# 05_kbd_pm.net
KiCad netlist of a schematic drawn in Altium Designer
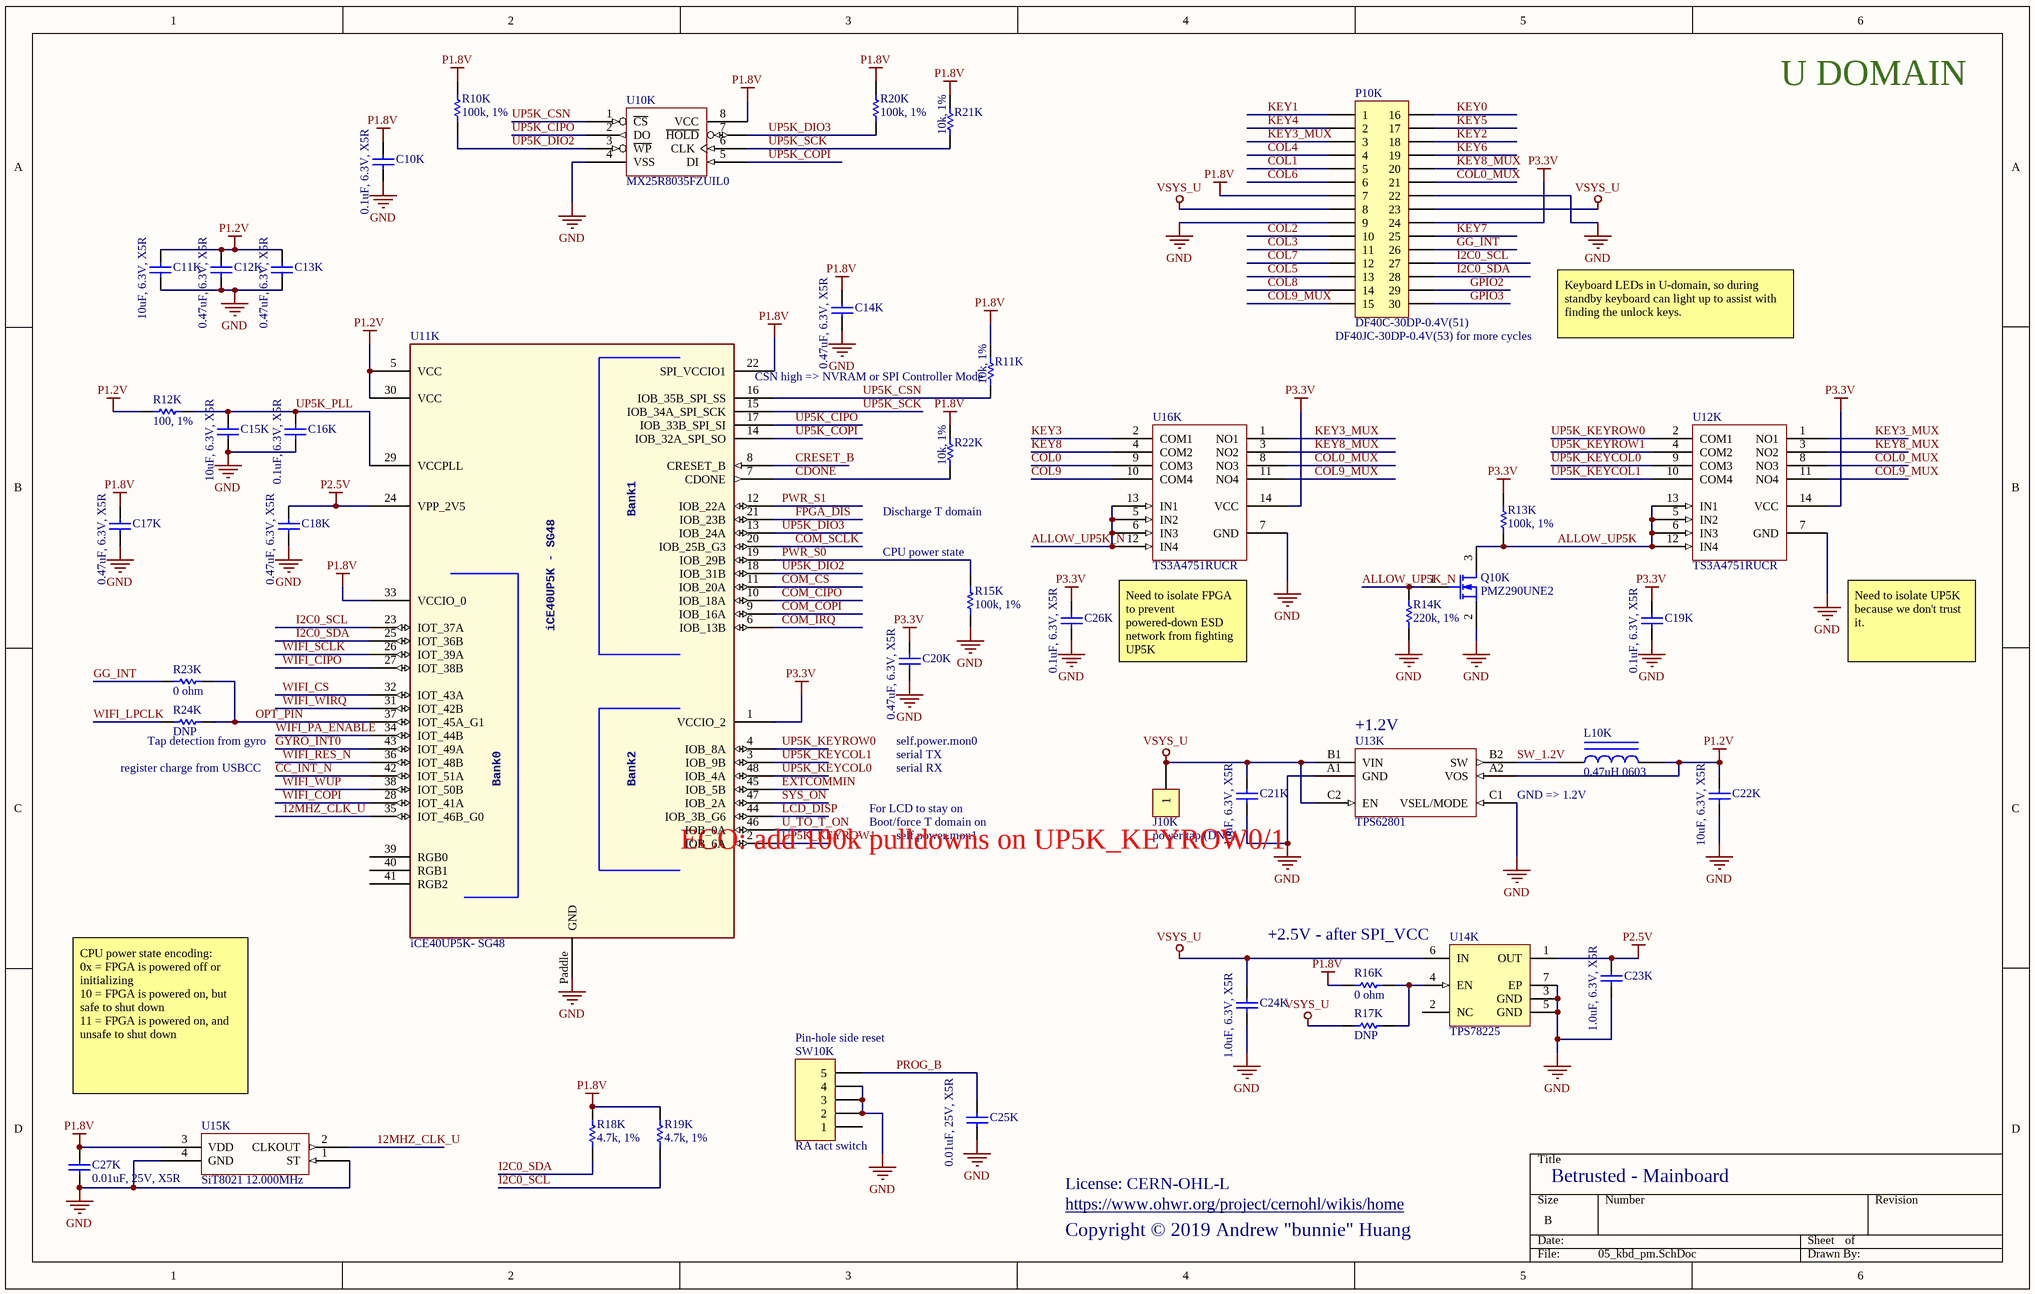
[diagram p0: 05_kbd_pm.SchDoc]

(export (version "E")
  (design (tool "Eeschema 10.0.6"))
  (components
    (comp (ref "C10K")
      (value "0.1uF, 6.3V, X5R")
      (footprint "B_CAP0201")
      (description "Capacitor (Semiconductor SIM Model)")
      (fields (field (name "MPN") "CL03A104KQ3NNNC"))
      (libsource (lib "Miscellaneous Devices") (part "Cap Semi"))
    )
    (comp (ref "C11K")
      (value "10uF, 6.3V, X5R")
      (footprint "B_CAP0603")
      (description "Capacitor (Semiconductor SIM Model)")
      (fields (field (name "MPN") "CL10A106MQ8NNNC"))
      (libsource (lib "Miscellaneous Devices") (part "Cap Semi"))
    )
    (comp (ref "C12K")
      (value "0.47uF, 6.3V, X5R")
      (footprint "B_CAP0201")
      (description "Capacitor (Semiconductor SIM Model)")
      (fields (field (name "MPN") "CL03A474KQ3NNNH"))
      (libsource (lib "Miscellaneous Devices") (part "Cap Semi"))
    )
    (comp (ref "C13K")
      (value "0.47uF, 6.3V, X5R")
      (footprint "B_CAP0201")
      (description "Capacitor (Semiconductor SIM Model)")
      (fields (field (name "MPN") "CL03A474KQ3NNNH"))
      (libsource (lib "Miscellaneous Devices") (part "Cap Semi"))
    )
    (comp (ref "C14K")
      (value "0.47uF, 6.3V, X5R")
      (footprint "B_CAP0201")
      (description "Capacitor (Semiconductor SIM Model)")
      (fields (field (name "MPN") "CL03A474KQ3NNNH"))
      (libsource (lib "Miscellaneous Devices") (part "Cap Semi"))
    )
    (comp (ref "C15K")
      (value "10uF, 6.3V, X5R")
      (footprint "B_CAP0603")
      (description "Capacitor (Semiconductor SIM Model)")
      (fields (field (name "MPN") "CL10A106MQ8NNNC"))
      (libsource (lib "Miscellaneous Devices") (part "Cap Semi"))
    )
    (comp (ref "C16K")
      (value "0.1uF, 6.3V, X5R")
      (footprint "B_CAP0201")
      (description "Capacitor (Semiconductor SIM Model)")
      (fields (field (name "MPN") "CL03A104KQ3NNNC"))
      (libsource (lib "Miscellaneous Devices") (part "Cap Semi"))
    )
    (comp (ref "C17K")
      (value "0.47uF, 6.3V, X5R")
      (footprint "B_CAP0201")
      (description "Capacitor (Semiconductor SIM Model)")
      (fields (field (name "MPN") "CL03A474KQ3NNNH"))
      (libsource (lib "Miscellaneous Devices") (part "Cap Semi"))
    )
    (comp (ref "C18K")
      (value "0.47uF, 6.3V, X5R")
      (footprint "B_CAP0201")
      (description "Capacitor (Semiconductor SIM Model)")
      (fields (field (name "MPN") "CL03A474KQ3NNNH"))
      (libsource (lib "Miscellaneous Devices") (part "Cap Semi"))
    )
    (comp (ref "C19K")
      (value "0.1uF, 6.3V, X5R")
      (footprint "B_CAP0201")
      (description "Capacitor (Semiconductor SIM Model)")
      (fields (field (name "MPN") "CL03A104KQ3NNNC"))
      (libsource (lib "Miscellaneous Devices") (part "Cap Semi"))
    )
    (comp (ref "C20K")
      (value "0.47uF, 6.3V, X5R")
      (footprint "B_CAP0201")
      (description "Capacitor (Semiconductor SIM Model)")
      (fields (field (name "MPN") "CL03A474KQ3NNNH"))
      (libsource (lib "Miscellaneous Devices") (part "Cap Semi"))
    )
    (comp (ref "C21K")
      (value "10uF, 6.3V, X5R")
      (footprint "B_CAP0603")
      (description "Capacitor (Semiconductor SIM Model)")
      (fields (field (name "MPN") "CL10A106MQ8NNNC"))
      (libsource (lib "Miscellaneous Devices") (part "Cap Semi"))
    )
    (comp (ref "C22K")
      (value "10uF, 6.3V, X5R")
      (footprint "B_CAP0603")
      (description "Capacitor (Semiconductor SIM Model)")
      (fields (field (name "MPN") "CL10A106MQ8NNNC"))
      (libsource (lib "Miscellaneous Devices") (part "Cap Semi"))
    )
    (comp (ref "C23K")
      (value "1.0uF, 6.3V, X5R")
      (footprint "B_CAP0201")
      (description "Capacitor (Semiconductor SIM Model)")
      (fields (field (name "MPN") "GRM033R60J105MEA2D"))
      (libsource (lib "Miscellaneous Devices") (part "Cap Semi"))
    )
    (comp (ref "C24K")
      (value "1.0uF, 6.3V, X5R")
      (footprint "B_CAP0201")
      (description "Capacitor (Semiconductor SIM Model)")
      (fields (field (name "MPN") "GRM033R60J105MEA2D"))
      (libsource (lib "Miscellaneous Devices") (part "Cap Semi"))
    )
    (comp (ref "C25K")
      (value "0.01uF, 25V, X5R")
      (footprint "B_RES0201")
      (description "Capacitor (Semiconductor SIM Model)")
      (fields (field (name "MPN") "GRM033R61E103KA12D"))
      (libsource (lib "Miscellaneous Devices") (part "Cap Semi"))
    )
    (comp (ref "C26K")
      (value "0.1uF, 6.3V, X5R")
      (footprint "B_CAP0201")
      (description "Capacitor (Semiconductor SIM Model)")
      (fields (field (name "MPN") "CL03A104KQ3NNNC"))
      (libsource (lib "Miscellaneous Devices") (part "Cap Semi"))
    )
    (comp (ref "C27K")
      (value "0.01uF, 25V, X5R")
      (footprint "B_RES0201")
      (description "Capacitor (Semiconductor SIM Model)")
      (fields (field (name "MPN") "GRM033R61E103KA12D"))
      (libsource (lib "Miscellaneous Devices") (part "Cap Semi"))
    )
    (comp (ref "J10K")
      (value "power tap (DNP)")
      (footprint "RESTAP-0603")
      (description "Connector")
      (fields (field (name "MPN") "DNP"))
      (libsource (lib "*") (part "CON1"))
    )
    (comp (ref "L10K")
      (value "0.47uH 0603")
      (footprint "B_IND0603")
      (description "Magnetic-Core Inductor")
      (fields (field (name "MPN") "TFM160808ALC-R47MTAA"))
      (libsource (lib "Miscellaneous Devices") (part "Inductor Iron"))
    )
    (comp (ref "P10K")
      (value "DF40C-30DP-0.4V(51)")
      (footprint "HRS_DF40C-30DP-0.4V(51)")
      (description "Header, 15-Pin, Dual row")
      (fields (field (name "PUBLISHER") "Altium Limited"))
      (libsource (lib "Miscellaneous Connectors") (part "Header 15X2A"))
    )
    (comp (ref "Q10K")
      (value "PMZ290UNE2")
      (footprint "SOT883")
      (description "N-Channel MOSFET")
      (fields (field (name "PUBLISHER") "Altium Limited"))
      (libsource (lib "Miscellaneous Devices") (part "MOSFET-N"))
    )
    (comp (ref "R10K")
      (value "100k, 1%")
      (footprint "B_RES0201")
      (description "Resistor")
      (fields (field (name "MPN") "ANY"))
      (libsource (lib "Miscellaneous Devices") (part "Res1"))
    )
    (comp (ref "R11K")
      (value "10k, 1%")
      (footprint "B_RES0201")
      (description "Resistor")
      (fields (field (name "MPN") "ANY"))
      (libsource (lib "Miscellaneous Devices") (part "Res1"))
    )
    (comp (ref "R12K")
      (value "100, 1%")
      (footprint "B_RES0402")
      (description "Resistor")
      (fields (field (name "MPN") "ANY"))
      (libsource (lib "Miscellaneous Devices") (part "Res1"))
    )
    (comp (ref "R13K")
      (value "100k, 1%")
      (footprint "B_RES0201")
      (description "Resistor")
      (fields (field (name "MPN") "ANY"))
      (libsource (lib "Miscellaneous Devices") (part "Res1"))
    )
    (comp (ref "R14K")
      (value "220k, 1%")
      (footprint "B_RES0201")
      (description "Resistor")
      (fields (field (name "MPN") "ANY"))
      (libsource (lib "Miscellaneous Devices") (part "Res1"))
    )
    (comp (ref "R15K")
      (value "100k, 1%")
      (footprint "B_RES0201")
      (description "Resistor")
      (fields (field (name "MPN") "ANY"))
      (libsource (lib "Miscellaneous Devices") (part "Res1"))
    )
    (comp (ref "R16K")
      (value "0 ohm")
      (footprint "B_RES0201")
      (description "Resistor")
      (fields (field (name "MPN") "ANY"))
      (libsource (lib "Miscellaneous Devices") (part "Res1"))
    )
    (comp (ref "R17K")
      (value "DNP")
      (footprint "B_RES0201")
      (description "Resistor")
      (fields (field (name "MPN") "ANY"))
      (libsource (lib "Miscellaneous Devices") (part "Res1"))
    )
    (comp (ref "R18K")
      (value "4.7k, 1%")
      (footprint "B_RES0201")
      (description "Resistor")
      (fields (field (name "MPN") "ANY"))
      (libsource (lib "Miscellaneous Devices") (part "Res1"))
    )
    (comp (ref "R19K")
      (value "4.7k, 1%")
      (footprint "B_RES0201")
      (description "Resistor")
      (fields (field (name "MPN") "ANY"))
      (libsource (lib "Miscellaneous Devices") (part "Res1"))
    )
    (comp (ref "R20K")
      (value "100k, 1%")
      (footprint "B_RES0201")
      (description "Resistor")
      (fields (field (name "MPN") "ANY"))
      (libsource (lib "Miscellaneous Devices") (part "Res1"))
    )
    (comp (ref "R21K")
      (value "10k, 1%")
      (footprint "B_RES0201")
      (description "Resistor")
      (fields (field (name "MPN") "ANY"))
      (libsource (lib "Miscellaneous Devices") (part "Res1"))
    )
    (comp (ref "R22K")
      (value "10k, 1%")
      (footprint "B_RES0201")
      (description "Resistor")
      (fields (field (name "MPN") "ANY"))
      (libsource (lib "Miscellaneous Devices") (part "Res1"))
    )
    (comp (ref "R23K")
      (value "0 ohm")
      (footprint "B_RES0201")
      (description "Resistor")
      (fields (field (name "MPN") "ANY"))
      (libsource (lib "Miscellaneous Devices") (part "Res1"))
    )
    (comp (ref "R24K")
      (value "DNP")
      (footprint "B_RES0201")
      (description "Resistor")
      (fields (field (name "MPN") "ANY"))
      (libsource (lib "Miscellaneous Devices") (part "Res1"))
    )
    (comp (ref "SW10K")
      (value "RA tact switch")
      (footprint "CK_KMS221GPLFS")
      (fields (field (name "MPN") "KMS221GPLFS") (field (name "PUBLISHER") "Altium Limited"))
      (libsource (lib "Miscellaneous Connectors") (part "Header 5"))
    )
    (comp (ref "U10K")
      (value "MX25R8035FZUIL0")
      (footprint "USON-8")
      (description "64Mbit SPI NOR FLASH")
      (libsource (lib "commonsch") (part "EN25P05-50GCP"))
    )
    (comp (ref "U11K")
      (value "iCE40UP5K- SG48")
      (footprint "UP5K_QFN127P600-8N")
      (fields (field (name "MPN") "ICE40UP5K-SG48I"))
      (libsource (lib "LATTICEPLDS_Library") (part "iCE40UP5K- SG48"))
    )
    (comp (ref "U12K")
      (value "TS3A4751RUCR")
      (footprint "QFN40P200X200X40-14L")
      (description "0.9 ohm low voltage, single supply, 4-channel SPST analog switch")
      (libsource (lib "commonsch-new") (part "TS3A4751RGYR"))
    )
    (comp (ref "U13K")
      (value "TPS62801")
      (footprint "BGA6C35P2X3_70X105X40_NSMD")
      (description "Buck regulator, 4MHz, 0.6A, 0.8V-1.55V, low Iq")
      (fields (field (name "MPN") "TPS62801YKAT"))
      (libsource (lib "altium-import") (part "root_0_TPS62801_"))
    )
    (comp (ref "U14K")
      (value "TPS78225")
      (footprint "TI-DRV6-1600X1000TP_V")
      (description "500nA Iq, 150mA LDO")
      (fields (field (name "MPN") "TPS78225DRVT"))
      (libsource (lib "TI-TPS78225-Q1DRV6-1600X1000TP") (part "TI-TPS78225-Q1DRV6-1600X1000TP"))
    )
    (comp (ref "U15K")
      (value "SiT8021 12.000MHz")
      (footprint "SiTIME_CSP")
      (description "1 to 26 MHz micropower oscillator")
      (fields (field (name "MPN") "SIT8021AI-J4-18S-12.000000E"))
      (libsource (lib "altium-import") (part "root_2_SiT8021_"))
    )
    (comp (ref "U16K")
      (value "TS3A4751RUCR")
      (footprint "QFN40P200X200X40-14L")
      (description "0.9 ohm low voltage, single supply, 4-channel SPST analog switch")
      (libsource (lib "commonsch-new") (part "TS3A4751RGYR"))
    )
  )
  (nets
    (net (code "1") (name "/12MHZ_CLK_U") (class "Default")
      (node (ref "U11K") (pin "35") (pinfunction "IOT_46B_G0_35") (pintype "bidirectional"))
      (node (ref "U15K") (pin "2") (pinfunction "CLKOUT_2") (pintype "output"))
    )
    (net (code "2") (name "/ALLOW_UP5K") (class "Default")
      (node (ref "Q10K") (pin "3") (pinfunction "D_3") (pintype "passive"))
      (node (ref "R13K") (pin "1") (pinfunction "1_1") (pintype "passive"))
      (node (ref "U12K") (pin "12") (pinfunction "IN4_12") (pintype "input"))
      (node (ref "U12K") (pin "13") (pinfunction "IN1_13") (pintype "input"))
      (node (ref "U12K") (pin "5") (pinfunction "IN2_5") (pintype "input"))
      (node (ref "U12K") (pin "6") (pinfunction "IN3_6") (pintype "input"))
    )
    (net (code "3") (name "/ALLOW_UP5K_N") (class "Default")
      (node (ref "Q10K") (pin "1") (pinfunction "G_1") (pintype "passive"))
      (node (ref "R14K") (pin "2") (pinfunction "2_2") (pintype "passive"))
      (node (ref "U16K") (pin "12") (pinfunction "IN4_12") (pintype "input"))
      (node (ref "U16K") (pin "13") (pinfunction "IN1_13") (pintype "input"))
      (node (ref "U16K") (pin "5") (pinfunction "IN2_5") (pintype "input"))
      (node (ref "U16K") (pin "6") (pinfunction "IN3_6") (pintype "input"))
    )
    (net (code "4") (name "/CC_INT_N") (class "Default")
      (node (ref "U11K") (pin "42") (pinfunction "IOT_51A_42") (pintype "bidirectional"))
    )
    (net (code "5") (name "/CDONE") (class "Default")
      (node (ref "R22K") (pin "2") (pinfunction "2_2") (pintype "passive"))
      (node (ref "U11K") (pin "7") (pinfunction "CDONE_7") (pintype "output"))
    )
    (net (code "6") (name "/COL0") (class "Default")
      (node (ref "U16K") (pin "9") (pinfunction "COM3_9") (pintype "passive"))
    )
    (net (code "7") (name "/COL0_MUX") (class "Default")
      (node (ref "P10K") (pin "21") (pinfunction "21_21") (pintype "passive"))
      (node (ref "U12K") (pin "8") (pinfunction "NO3_8") (pintype "passive"))
      (node (ref "U16K") (pin "8") (pinfunction "NO3_8") (pintype "passive"))
    )
    (net (code "8") (name "/COL1") (class "Default")
      (node (ref "P10K") (pin "5") (pinfunction "5_5") (pintype "passive"))
    )
    (net (code "9") (name "/COL2") (class "Default")
      (node (ref "P10K") (pin "10") (pinfunction "10_10") (pintype "passive"))
    )
    (net (code "10") (name "/COL3") (class "Default")
      (node (ref "P10K") (pin "11") (pinfunction "11_11") (pintype "passive"))
    )
    (net (code "11") (name "/COL4") (class "Default")
      (node (ref "P10K") (pin "4") (pinfunction "4_4") (pintype "passive"))
    )
    (net (code "12") (name "/COL5") (class "Default")
      (node (ref "P10K") (pin "13") (pinfunction "13_13") (pintype "passive"))
    )
    (net (code "13") (name "/COL6") (class "Default")
      (node (ref "P10K") (pin "6") (pinfunction "6_6") (pintype "passive"))
    )
    (net (code "14") (name "/COL7") (class "Default")
      (node (ref "P10K") (pin "12") (pinfunction "12_12") (pintype "passive"))
    )
    (net (code "15") (name "/COL8") (class "Default")
      (node (ref "P10K") (pin "14") (pinfunction "14_14") (pintype "passive"))
    )
    (net (code "16") (name "/COL9") (class "Default")
      (node (ref "U16K") (pin "10") (pinfunction "COM4_10") (pintype "passive"))
    )
    (net (code "17") (name "/COL9_MUX") (class "Default")
      (node (ref "P10K") (pin "15") (pinfunction "15_15") (pintype "passive"))
      (node (ref "U12K") (pin "11") (pinfunction "NO4_11") (pintype "passive"))
      (node (ref "U16K") (pin "11") (pinfunction "NO4_11") (pintype "passive"))
    )
    (net (code "18") (name "/COM_CIPO") (class "Default")
      (node (ref "U11K") (pin "10") (pinfunction "IOB_18A_10") (pintype "bidirectional"))
    )
    (net (code "19") (name "/COM_COPI") (class "Default")
      (node (ref "U11K") (pin "9") (pinfunction "IOB_16A_9") (pintype "bidirectional"))
    )
    (net (code "20") (name "/COM_CS") (class "Default")
      (node (ref "U11K") (pin "11") (pinfunction "IOB_20A_11") (pintype "bidirectional"))
    )
    (net (code "21") (name "/COM_IRQ") (class "Default")
      (node (ref "U11K") (pin "6") (pinfunction "IOB_13B_6") (pintype "bidirectional"))
    )
    (net (code "22") (name "/COM_SCLK") (class "Default")
      (node (ref "U11K") (pin "20") (pinfunction "IOB_25B_G3_20") (pintype "bidirectional"))
    )
    (net (code "23") (name "/CRESET_B") (class "Default")
      (node (ref "U11K") (pin "8") (pinfunction "CRESET_B_8") (pintype "input"))
    )
    (net (code "24") (name "/EXTCOMMIN") (class "Default")
      (node (ref "U11K") (pin "45") (pinfunction "IOB_5B_45") (pintype "bidirectional"))
    )
    (net (code "25") (name "/FPGA_DIS") (class "Default")
      (node (ref "U11K") (pin "21") (pinfunction "IOB_23B_21") (pintype "bidirectional"))
    )
    (net (code "26") (name "/GG_INT") (class "Default")
      (node (ref "P10K") (pin "26") (pinfunction "26_26") (pintype "passive"))
      (node (ref "R23K") (pin "1") (pinfunction "1_1") (pintype "passive"))
    )
    (net (code "27") (name "/GPIO2") (class "Default")
      (node (ref "P10K") (pin "29") (pinfunction "29_29") (pintype "passive"))
    )
    (net (code "28") (name "/GPIO3") (class "Default")
      (node (ref "P10K") (pin "30") (pinfunction "30_30") (pintype "passive"))
    )
    (net (code "29") (name "/GYRO_INT0") (class "Default")
      (node (ref "U11K") (pin "43") (pinfunction "IOT_49A_43") (pintype "bidirectional"))
    )
    (net (code "30") (name "/I2C0_SCL") (class "Default")
      (node (ref "P10K") (pin "27") (pinfunction "27_27") (pintype "passive"))
      (node (ref "R19K") (pin "1") (pinfunction "1_1") (pintype "passive"))
      (node (ref "U11K") (pin "23") (pinfunction "IOT_37A_23") (pintype "bidirectional"))
    )
    (net (code "31") (name "/I2C0_SDA") (class "Default")
      (node (ref "P10K") (pin "28") (pinfunction "28_28") (pintype "passive"))
      (node (ref "R18K") (pin "1") (pinfunction "1_1") (pintype "passive"))
      (node (ref "U11K") (pin "25") (pinfunction "IOT_36B_25") (pintype "bidirectional"))
    )
    (net (code "32") (name "/KEY0") (class "Default")
      (node (ref "P10K") (pin "16") (pinfunction "16_16") (pintype "passive"))
    )
    (net (code "33") (name "/KEY1") (class "Default")
      (node (ref "P10K") (pin "1") (pinfunction "1_1") (pintype "passive"))
    )
    (net (code "34") (name "/KEY2") (class "Default")
      (node (ref "P10K") (pin "18") (pinfunction "18_18") (pintype "passive"))
    )
    (net (code "35") (name "/KEY3") (class "Default")
      (node (ref "U16K") (pin "2") (pinfunction "COM1_2") (pintype "passive"))
    )
    (net (code "36") (name "/KEY3_MUX") (class "Default")
      (node (ref "P10K") (pin "3") (pinfunction "3_3") (pintype "passive"))
      (node (ref "U12K") (pin "1") (pinfunction "NO1_1") (pintype "passive"))
      (node (ref "U16K") (pin "1") (pinfunction "NO1_1") (pintype "passive"))
    )
    (net (code "37") (name "/KEY4") (class "Default")
      (node (ref "P10K") (pin "2") (pinfunction "2_2") (pintype "passive"))
    )
    (net (code "38") (name "/KEY5") (class "Default")
      (node (ref "P10K") (pin "17") (pinfunction "17_17") (pintype "passive"))
    )
    (net (code "39") (name "/KEY6") (class "Default")
      (node (ref "P10K") (pin "19") (pinfunction "19_19") (pintype "passive"))
    )
    (net (code "40") (name "/KEY7") (class "Default")
      (node (ref "P10K") (pin "25") (pinfunction "25_25") (pintype "passive"))
    )
    (net (code "41") (name "/KEY8") (class "Default")
      (node (ref "U16K") (pin "4") (pinfunction "COM2_4") (pintype "passive"))
    )
    (net (code "42") (name "/KEY8_MUX") (class "Default")
      (node (ref "P10K") (pin "20") (pinfunction "20_20") (pintype "passive"))
      (node (ref "U12K") (pin "3") (pinfunction "NO2_3") (pintype "passive"))
      (node (ref "U16K") (pin "3") (pinfunction "NO2_3") (pintype "passive"))
    )
    (net (code "43") (name "/LCD_DISP") (class "Default")
      (node (ref "U11K") (pin "44") (pinfunction "IOB_3B_G6_44") (pintype "bidirectional"))
    )
    (net (code "44") (name "/OPT_PIN") (class "Default")
      (node (ref "R23K") (pin "2") (pinfunction "2_2") (pintype "passive"))
      (node (ref "R24K") (pin "2") (pinfunction "2_2") (pintype "passive"))
      (node (ref "U11K") (pin "37") (pinfunction "IOT_45A_G1_37") (pintype "bidirectional"))
    )
    (net (code "45") (name "/PROG_B") (class "Default")
      (node (ref "C25K") (pin "1") (pinfunction "1_1") (pintype "passive"))
      (node (ref "SW10K") (pin "5") (pinfunction "5_5") (pintype "passive"))
    )
    (net (code "46") (name "/PWR_S0") (class "Default")
      (node (ref "R15K") (pin "2") (pinfunction "2_2") (pintype "passive"))
      (node (ref "U11K") (pin "19") (pinfunction "IOB_29B_19") (pintype "bidirectional"))
    )
    (net (code "47") (name "/PWR_S1") (class "Default")
      (node (ref "U11K") (pin "12") (pinfunction "IOB_22A_12") (pintype "bidirectional"))
    )
    (net (code "48") (name "/SW_1.2V") (class "Default")
      (node (ref "L10K") (pin "1") (pinfunction "1_1") (pintype "passive"))
      (node (ref "U13K") (pin "B2") (pinfunction "SW_B2") (pintype "output"))
    )
    (net (code "49") (name "/SYS_ON") (class "Default")
      (node (ref "U11K") (pin "47") (pinfunction "IOB_2A_47") (pintype "bidirectional"))
    )
    (net (code "50") (name "/UP5K_CIPO") (class "Default")
      (node (ref "U10K") (pin "2") (pinfunction "DO_2") (pintype "output"))
      (node (ref "U11K") (pin "17") (pinfunction "IOB_33B_SPI_SI_17") (pintype "passive"))
    )
    (net (code "51") (name "/UP5K_COPI") (class "Default")
      (node (ref "U10K") (pin "5") (pinfunction "DI_5") (pintype "input"))
      (node (ref "U11K") (pin "14") (pinfunction "IOB_32A_SPI_SO_14") (pintype "passive"))
    )
    (net (code "52") (name "/UP5K_CSN") (class "Default")
      (node (ref "R11K") (pin "2") (pinfunction "2_2") (pintype "passive"))
      (node (ref "U10K") (pin "1") (pinfunction "~{CS}_1") (pintype "input"))
      (node (ref "U11K") (pin "16") (pinfunction "IOB_35B_SPI_SS_16") (pintype "passive"))
    )
    (net (code "53") (name "/UP5K_DIO2") (class "Default")
      (node (ref "R10K") (pin "1") (pinfunction "1_1") (pintype "passive"))
      (node (ref "U10K") (pin "3") (pinfunction "~{WP}_3") (pintype "input"))
      (node (ref "U11K") (pin "18") (pinfunction "IOB_31B_18") (pintype "bidirectional"))
    )
    (net (code "54") (name "/UP5K_DIO3") (class "Default")
      (node (ref "R20K") (pin "1") (pinfunction "1_1") (pintype "passive"))
      (node (ref "U10K") (pin "7") (pinfunction "~{HOLD}_7") (pintype "bidirectional"))
      (node (ref "U11K") (pin "13") (pinfunction "IOB_24A_13") (pintype "bidirectional"))
    )
    (net (code "55") (name "/UP5K_KEYCOL0") (class "Default")
      (node (ref "U11K") (pin "48") (pinfunction "IOB_4A_48") (pintype "bidirectional"))
      (node (ref "U12K") (pin "9") (pinfunction "COM3_9") (pintype "passive"))
    )
    (net (code "56") (name "/UP5K_KEYCOL1") (class "Default")
      (node (ref "U11K") (pin "3") (pinfunction "IOB_9B_3") (pintype "bidirectional"))
      (node (ref "U12K") (pin "10") (pinfunction "COM4_10") (pintype "passive"))
    )
    (net (code "57") (name "/UP5K_KEYROW0") (class "Default")
      (node (ref "U11K") (pin "4") (pinfunction "IOB_8A_4") (pintype "bidirectional"))
      (node (ref "U12K") (pin "2") (pinfunction "COM1_2") (pintype "passive"))
    )
    (net (code "58") (name "/UP5K_KEYROW1") (class "Default")
      (node (ref "U11K") (pin "2") (pinfunction "IOB_6A_2") (pintype "bidirectional"))
      (node (ref "U12K") (pin "4") (pinfunction "COM2_4") (pintype "passive"))
    )
    (net (code "59") (name "/UP5K_PLL") (class "Default")
      (node (ref "C15K") (pin "1") (pinfunction "1_1") (pintype "passive"))
      (node (ref "C16K") (pin "1") (pinfunction "1_1") (pintype "passive"))
      (node (ref "R12K") (pin "1") (pinfunction "1_1") (pintype "passive"))
      (node (ref "U11K") (pin "29") (pinfunction "VCCPLL_29") (pintype "power_in"))
    )
    (net (code "60") (name "/UP5K_SCK") (class "Default")
      (node (ref "R21K") (pin "2") (pinfunction "2_2") (pintype "passive"))
      (node (ref "U10K") (pin "6") (pinfunction "CLK_6") (pintype "input"))
      (node (ref "U11K") (pin "15") (pinfunction "IOB_34A_SPI_SCK_15") (pintype "passive"))
    )
    (net (code "61") (name "/U_TO_T_ON") (class "Default")
      (node (ref "U11K") (pin "46") (pinfunction "IOB_0A_46") (pintype "bidirectional"))
    )
    (net (code "62") (name "/WIFI_CIPO") (class "Default")
      (node (ref "U11K") (pin "27") (pinfunction "IOT_38B_27") (pintype "bidirectional"))
    )
    (net (code "63") (name "/WIFI_COPI") (class "Default")
      (node (ref "U11K") (pin "28") (pinfunction "IOT_41A_28") (pintype "bidirectional"))
    )
    (net (code "64") (name "/WIFI_CS") (class "Default")
      (node (ref "U11K") (pin "32") (pinfunction "IOT_43A_32") (pintype "bidirectional"))
    )
    (net (code "65") (name "/WIFI_LPCLK") (class "Default")
      (node (ref "R24K") (pin "1") (pinfunction "1_1") (pintype "passive"))
    )
    (net (code "66") (name "/WIFI_PA_ENABLE") (class "Default")
      (node (ref "U11K") (pin "34") (pinfunction "IOT_44B_34") (pintype "bidirectional"))
    )
    (net (code "67") (name "/WIFI_RES_N") (class "Default")
      (node (ref "U11K") (pin "36") (pinfunction "IOT_48B_36") (pintype "bidirectional"))
    )
    (net (code "68") (name "/WIFI_SCLK") (class "Default")
      (node (ref "U11K") (pin "26") (pinfunction "IOT_39A_26") (pintype "bidirectional"))
    )
    (net (code "69") (name "/WIFI_WIRQ") (class "Default")
      (node (ref "U11K") (pin "31") (pinfunction "IOT_42B_31") (pintype "bidirectional"))
    )
    (net (code "70") (name "/WIFI_WUP") (class "Default")
      (node (ref "U11K") (pin "38") (pinfunction "IOT_50B_38") (pintype "bidirectional"))
    )
    (net (code "71") (name "GND") (class "Default")
      (node (ref "C10K") (pin "2") (pinfunction "2_2") (pintype "passive"))
      (node (ref "C11K") (pin "2") (pinfunction "2_2") (pintype "passive"))
      (node (ref "C12K") (pin "2") (pinfunction "2_2") (pintype "passive"))
      (node (ref "C13K") (pin "2") (pinfunction "2_2") (pintype "passive"))
      (node (ref "C14K") (pin "2") (pinfunction "2_2") (pintype "passive"))
      (node (ref "C15K") (pin "2") (pinfunction "2_2") (pintype "passive"))
      (node (ref "C16K") (pin "2") (pinfunction "2_2") (pintype "passive"))
      (node (ref "C17K") (pin "2") (pinfunction "2_2") (pintype "passive"))
      (node (ref "C18K") (pin "2") (pinfunction "2_2") (pintype "passive"))
      (node (ref "C19K") (pin "2") (pinfunction "2_2") (pintype "passive"))
      (node (ref "C20K") (pin "2") (pinfunction "2_2") (pintype "passive"))
      (node (ref "C21K") (pin "2") (pinfunction "2_2") (pintype "passive"))
      (node (ref "C22K") (pin "2") (pinfunction "2_2") (pintype "passive"))
      (node (ref "C23K") (pin "2") (pinfunction "2_2") (pintype "passive"))
      (node (ref "C24K") (pin "2") (pinfunction "2_2") (pintype "passive"))
      (node (ref "C25K") (pin "2") (pinfunction "2_2") (pintype "passive"))
      (node (ref "C26K") (pin "2") (pinfunction "2_2") (pintype "passive"))
      (node (ref "C27K") (pin "2") (pinfunction "2_2") (pintype "passive"))
      (node (ref "P10K") (pin "22") (pinfunction "22_22") (pintype "passive"))
      (node (ref "P10K") (pin "9") (pinfunction "9_9") (pintype "passive"))
      (node (ref "Q10K") (pin "2") (pinfunction "S_2") (pintype "passive"))
      (node (ref "R14K") (pin "1") (pinfunction "1_1") (pintype "passive"))
      (node (ref "R15K") (pin "1") (pinfunction "1_1") (pintype "passive"))
      (node (ref "SW10K") (pin "2") (pinfunction "2_2") (pintype "passive"))
      (node (ref "SW10K") (pin "3") (pinfunction "3_3") (pintype "passive"))
      (node (ref "SW10K") (pin "4") (pinfunction "4_4") (pintype "passive"))
      (node (ref "U10K") (pin "4") (pinfunction "VSS_4") (pintype "power_in"))
      (node (ref "U11K") (pin "Paddle") (pinfunction "GND_Paddle") (pintype "power_in"))
      (node (ref "U12K") (pin "7") (pinfunction "GND_7") (pintype "power_in"))
      (node (ref "U13K") (pin "A1") (pinfunction "GND_A1") (pintype "power_in"))
      (node (ref "U13K") (pin "C1") (pinfunction "VSEL/MODE_C1") (pintype "input"))
      (node (ref "U14K") (pin "3") (pinfunction "GND_3") (pintype "power_in"))
      (node (ref "U14K") (pin "5") (pinfunction "GND_5") (pintype "power_in"))
      (node (ref "U14K") (pin "7") (pinfunction "EP_7") (pintype "power_in"))
      (node (ref "U15K") (pin "1") (pinfunction "ST_1") (pintype "input"))
      (node (ref "U15K") (pin "4") (pinfunction "GND_4") (pintype "power_in"))
      (node (ref "U16K") (pin "7") (pinfunction "GND_7") (pintype "power_in"))
    )
    (net (code "72") (name "Net-(U14K-EN)") (class "Default")
      (node (ref "R16K") (pin "2") (pinfunction "2_2") (pintype "passive"))
      (node (ref "R17K") (pin "2") (pinfunction "2_2") (pintype "passive"))
      (node (ref "U14K") (pin "4") (pinfunction "EN_4") (pintype "input"))
    )
    (net (code "73") (name "P1.2V") (class "Default")
      (node (ref "C11K") (pin "1") (pinfunction "1_1") (pintype "passive"))
      (node (ref "C12K") (pin "1") (pinfunction "1_1") (pintype "passive"))
      (node (ref "C13K") (pin "1") (pinfunction "1_1") (pintype "passive"))
      (node (ref "C22K") (pin "1") (pinfunction "1_1") (pintype "passive"))
      (node (ref "L10K") (pin "2") (pinfunction "2_2") (pintype "passive"))
      (node (ref "R12K") (pin "2") (pinfunction "2_2") (pintype "passive"))
      (node (ref "U11K") (pin "30") (pinfunction "VCC_30") (pintype "power_in"))
      (node (ref "U11K") (pin "5") (pinfunction "VCC_5") (pintype "power_in"))
      (node (ref "U13K") (pin "A2") (pinfunction "VOS_A2") (pintype "input"))
    )
    (net (code "74") (name "P1.8V") (class "Default")
      (node (ref "C10K") (pin "1") (pinfunction "1_1") (pintype "passive"))
      (node (ref "C14K") (pin "1") (pinfunction "1_1") (pintype "passive"))
      (node (ref "C17K") (pin "1") (pinfunction "1_1") (pintype "passive"))
      (node (ref "C27K") (pin "1") (pinfunction "1_1") (pintype "passive"))
      (node (ref "P10K") (pin "7") (pinfunction "7_7") (pintype "passive"))
      (node (ref "R10K") (pin "2") (pinfunction "2_2") (pintype "passive"))
      (node (ref "R11K") (pin "1") (pinfunction "1_1") (pintype "passive"))
      (node (ref "R16K") (pin "1") (pinfunction "1_1") (pintype "passive"))
      (node (ref "R18K") (pin "2") (pinfunction "2_2") (pintype "passive"))
      (node (ref "R19K") (pin "2") (pinfunction "2_2") (pintype "passive"))
      (node (ref "R20K") (pin "2") (pinfunction "2_2") (pintype "passive"))
      (node (ref "R21K") (pin "1") (pinfunction "1_1") (pintype "passive"))
      (node (ref "R22K") (pin "1") (pinfunction "1_1") (pintype "passive"))
      (node (ref "U10K") (pin "8") (pinfunction "VCC_8") (pintype "power_in"))
      (node (ref "U11K") (pin "22") (pinfunction "SPI_VCCIO1_22") (pintype "power_in"))
      (node (ref "U11K") (pin "33") (pinfunction "VCCIO_0_33") (pintype "power_in"))
      (node (ref "U15K") (pin "3") (pinfunction "VDD_3") (pintype "power_in"))
    )
    (net (code "75") (name "P2.5V") (class "Default")
      (node (ref "C18K") (pin "1") (pinfunction "1_1") (pintype "passive"))
      (node (ref "C23K") (pin "1") (pinfunction "1_1") (pintype "passive"))
      (node (ref "U11K") (pin "24") (pinfunction "VPP_2V5_24") (pintype "power_in"))
      (node (ref "U14K") (pin "1") (pinfunction "OUT_1") (pintype "power_in"))
    )
    (net (code "76") (name "P3.3V") (class "Default")
      (node (ref "C19K") (pin "1") (pinfunction "1_1") (pintype "passive"))
      (node (ref "C20K") (pin "1") (pinfunction "1_1") (pintype "passive"))
      (node (ref "C26K") (pin "1") (pinfunction "1_1") (pintype "passive"))
      (node (ref "P10K") (pin "24") (pinfunction "24_24") (pintype "passive"))
      (node (ref "R13K") (pin "2") (pinfunction "2_2") (pintype "passive"))
      (node (ref "U11K") (pin "1") (pinfunction "VCCIO_2_1") (pintype "power_in"))
      (node (ref "U12K") (pin "14") (pinfunction "VCC_14") (pintype "power_in"))
      (node (ref "U16K") (pin "14") (pinfunction "VCC_14") (pintype "power_in"))
    )
    (net (code "77") (name "VSYS_U") (class "Default")
      (node (ref "C21K") (pin "1") (pinfunction "1_1") (pintype "passive"))
      (node (ref "C24K") (pin "1") (pinfunction "1_1") (pintype "passive"))
      (node (ref "J10K") (pin "1") (pinfunction "1_1") (pintype "passive"))
      (node (ref "P10K") (pin "23") (pinfunction "23_23") (pintype "passive"))
      (node (ref "P10K") (pin "8") (pinfunction "8_8") (pintype "passive"))
      (node (ref "R17K") (pin "1") (pinfunction "1_1") (pintype "passive"))
      (node (ref "U13K") (pin "B1") (pinfunction "VIN_B1") (pintype "power_in"))
      (node (ref "U13K") (pin "C2") (pinfunction "EN_C2") (pintype "input"))
      (node (ref "U14K") (pin "6") (pinfunction "IN_6") (pintype "power_in"))
    )
    (net (code "78") (name "unconnected-(SW10K-Pad1)") (class "Default")
      (node (ref "SW10K") (pin "1") (pinfunction "1_1") (pintype "passive"))
    )
    (net (code "79") (name "unconnected-(U11K-RGB0-Pad39)") (class "Default")
      (node (ref "U11K") (pin "39") (pinfunction "RGB0_39") (pintype "open_collector"))
    )
    (net (code "80") (name "unconnected-(U11K-RGB1-Pad40)") (class "Default")
      (node (ref "U11K") (pin "40") (pinfunction "RGB1_40") (pintype "open_collector"))
    )
    (net (code "81") (name "unconnected-(U11K-RGB2-Pad41)") (class "Default")
      (node (ref "U11K") (pin "41") (pinfunction "RGB2_41") (pintype "open_collector"))
    )
    (net (code "82") (name "unconnected-(U14K-NC-Pad2)") (class "Default")
      (node (ref "U14K") (pin "2") (pinfunction "NC_2") (pintype "passive"))
    )
  )
)
